# alarmClock.net
KiCad netlist of a schematic drawn in EAGLE
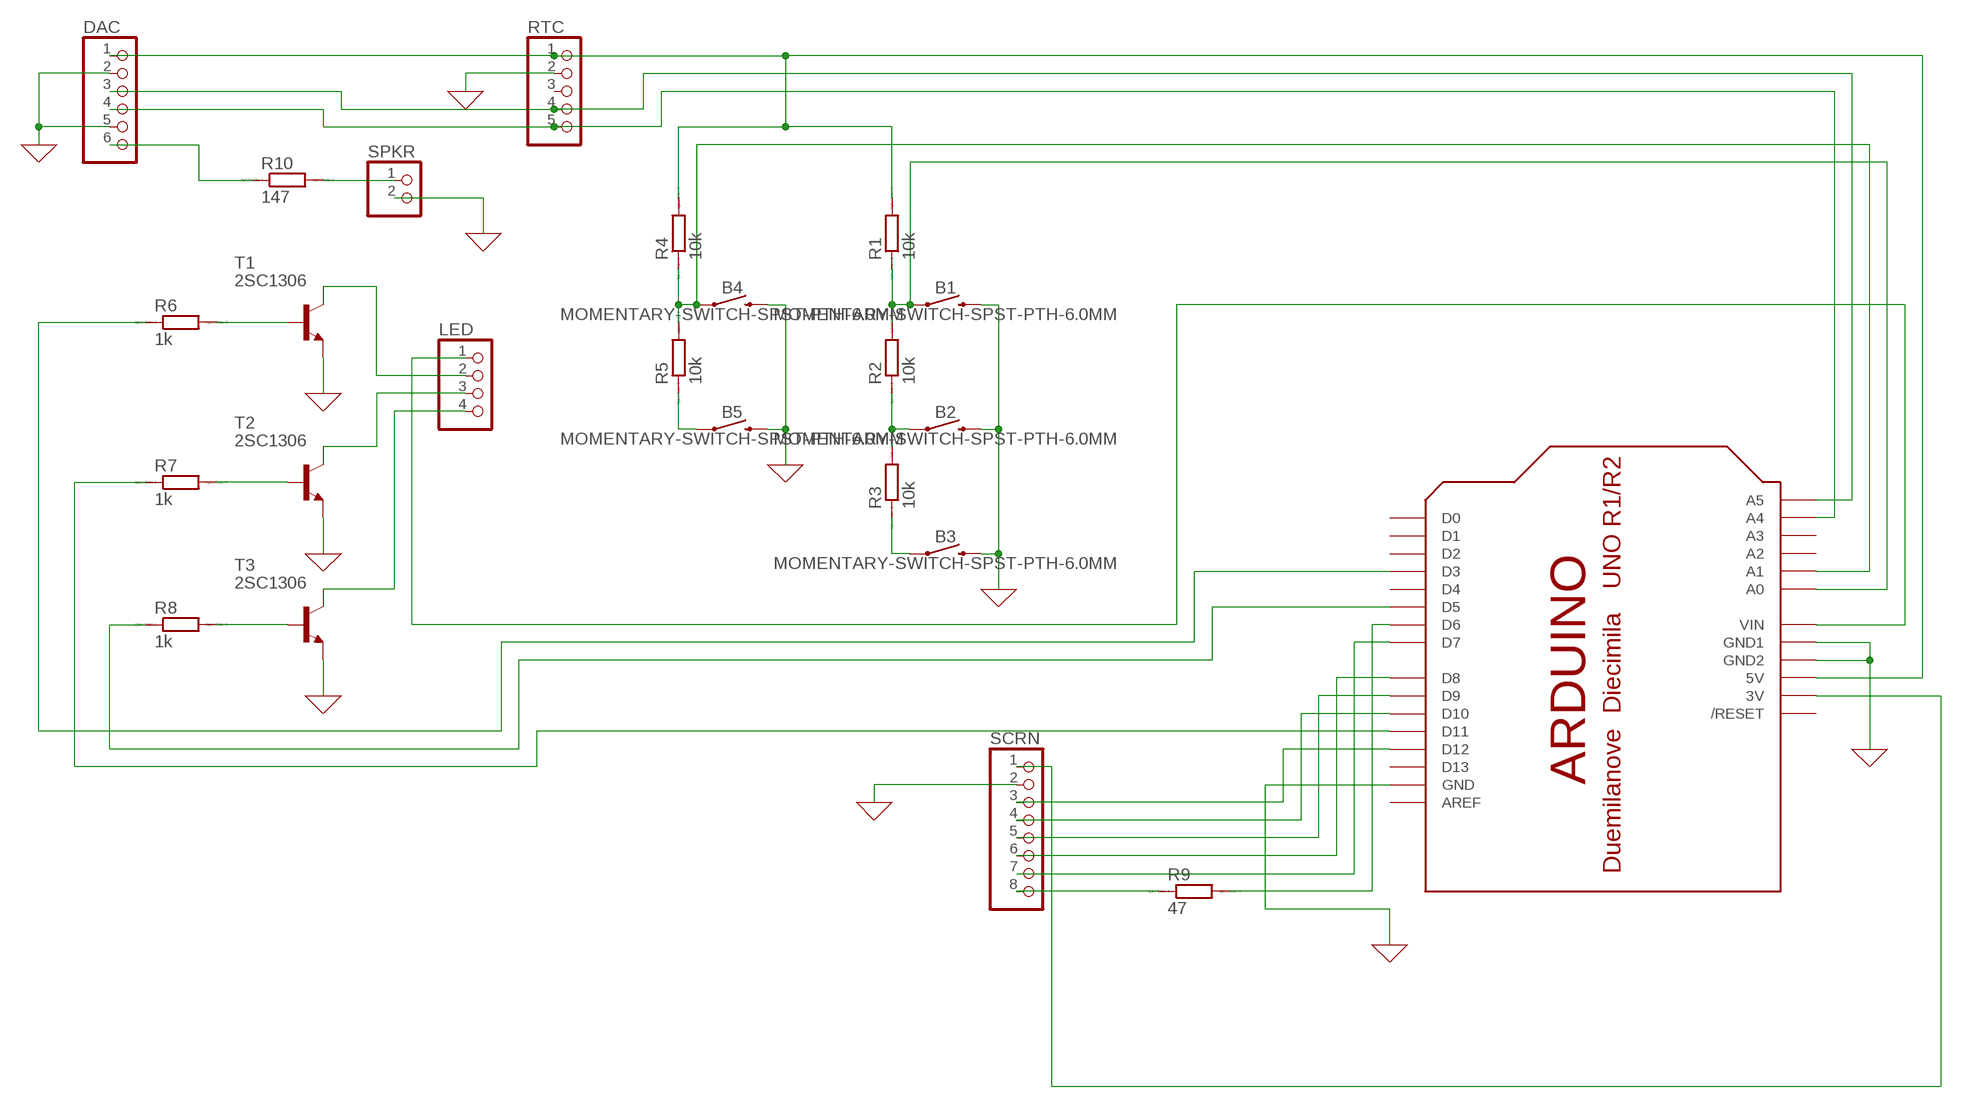
[diagram p0: schematic, sheet 1]

(export (version "E")
  (design (tool "Eeschema 10.0.6"))
  (components
    (comp (ref "B1")
      (value "MOMENTARY-SWITCH-SPST-PTH-6.0MM")
      (footprint "eagle-import:TACTILE_SWITCH_PTH_6.0MM")
      (libsource (lib "eagle-import") (part "MOMENTARY-SWITCH-SPST-PTH-6.0MM"))
    )
    (comp (ref "B2")
      (value "MOMENTARY-SWITCH-SPST-PTH-6.0MM")
      (footprint "eagle-import:TACTILE_SWITCH_PTH_6.0MM")
      (libsource (lib "eagle-import") (part "MOMENTARY-SWITCH-SPST-PTH-6.0MM"))
    )
    (comp (ref "B3")
      (value "MOMENTARY-SWITCH-SPST-PTH-6.0MM")
      (footprint "eagle-import:TACTILE_SWITCH_PTH_6.0MM")
      (libsource (lib "eagle-import") (part "MOMENTARY-SWITCH-SPST-PTH-6.0MM"))
    )
    (comp (ref "B4")
      (value "MOMENTARY-SWITCH-SPST-PTH-6.0MM")
      (footprint "eagle-import:TACTILE_SWITCH_PTH_6.0MM")
      (libsource (lib "eagle-import") (part "MOMENTARY-SWITCH-SPST-PTH-6.0MM"))
    )
    (comp (ref "B5")
      (value "MOMENTARY-SWITCH-SPST-PTH-6.0MM")
      (footprint "eagle-import:TACTILE_SWITCH_PTH_6.0MM")
      (libsource (lib "eagle-import") (part "MOMENTARY-SWITCH-SPST-PTH-6.0MM"))
    )
    (comp (ref "DAC")
      (value "PINHD-1X6")
      (footprint "eagle-import:1X06")
      (libsource (lib "eagle-import") (part "PINHD-1X6"))
    )
    (comp (ref "LED")
      (value "PINHD-1X4")
      (footprint "eagle-import:1X04")
      (libsource (lib "eagle-import") (part "PINHD-1X4"))
    )
    (comp (ref "R1")
      (value "10k")
      (footprint "eagle-import:0204_7")
      (libsource (lib "eagle-import") (part "R0204/7"))
    )
    (comp (ref "R2")
      (value "10k")
      (footprint "eagle-import:0204_7")
      (libsource (lib "eagle-import") (part "R0204/7"))
    )
    (comp (ref "R3")
      (value "10k")
      (footprint "eagle-import:0204_7")
      (libsource (lib "eagle-import") (part "R0204/7"))
    )
    (comp (ref "R4")
      (value "10k")
      (footprint "eagle-import:0204_7")
      (libsource (lib "eagle-import") (part "R0204/7"))
    )
    (comp (ref "R5")
      (value "10k")
      (footprint "eagle-import:0204_7")
      (libsource (lib "eagle-import") (part "R0204/7"))
    )
    (comp (ref "R6")
      (value "1k")
      (footprint "eagle-import:0204_7")
      (libsource (lib "eagle-import") (part "R0204/7"))
    )
    (comp (ref "R7")
      (value "1k")
      (footprint "eagle-import:0204_7")
      (libsource (lib "eagle-import") (part "R0204/7"))
    )
    (comp (ref "R8")
      (value "1k")
      (footprint "eagle-import:0204_7")
      (libsource (lib "eagle-import") (part "R0204/7"))
    )
    (comp (ref "R9")
      (value "47")
      (footprint "eagle-import:0204_7")
      (libsource (lib "eagle-import") (part "R0204/7"))
    )
    (comp (ref "R10")
      (value "147")
      (footprint "eagle-import:0204_7")
      (libsource (lib "eagle-import") (part "R0204/7"))
    )
    (comp (ref "RTC")
      (value "PINHD-1X5")
      (footprint "eagle-import:1X05")
      (libsource (lib "eagle-import") (part "PINHD-1X5"))
    )
    (comp (ref "SCRN")
      (value "PINHD-1X8")
      (footprint "eagle-import:1X08")
      (libsource (lib "eagle-import") (part "PINHD-1X8"))
    )
    (comp (ref "SPKR")
      (value "PINHD-1X2")
      (footprint "eagle-import:1X02")
      (libsource (lib "eagle-import") (part "PINHD-1X2"))
    )
    (comp (ref "T1")
      (value "2SC1306")
      (footprint "eagle-import:TO220BV")
      (libsource (lib "eagle-import") (part "2SC1306"))
    )
    (comp (ref "T2")
      (value "2SC1306")
      (footprint "eagle-import:TO220BV")
      (libsource (lib "eagle-import") (part "2SC1306"))
    )
    (comp (ref "T3")
      (value "2SC1306")
      (footprint "eagle-import:TO220BV")
      (libsource (lib "eagle-import") (part "2SC1306"))
    )
    (comp (ref "U$1")
      (value "ARDUINOUNO")
      (footprint "eagle-import:ARDUINO")
      (libsource (lib "eagle-import") (part "ARDUINOUNO"))
    )
  )
  (nets
    (net (code "1") (name "GND") (class "Default")
      (node (ref "B1") (pin "3") (pinfunction "2_3") (pintype "passive"))
      (node (ref "B2") (pin "3") (pinfunction "2_3") (pintype "passive"))
      (node (ref "B3") (pin "3") (pinfunction "2_3") (pintype "passive"))
      (node (ref "B4") (pin "3") (pinfunction "2_3") (pintype "passive"))
      (node (ref "B5") (pin "3") (pinfunction "2_3") (pintype "passive"))
      (node (ref "DAC") (pin "2") (pinfunction "2_2") (pintype "passive"))
      (node (ref "DAC") (pin "5") (pinfunction "5_5") (pintype "passive"))
      (node (ref "RTC") (pin "2") (pinfunction "2_2") (pintype "passive"))
      (node (ref "SCRN") (pin "2") (pinfunction "2_2") (pintype "passive"))
      (node (ref "SPKR") (pin "2") (pinfunction "2_2") (pintype "passive"))
      (node (ref "T1") (pin "3") (pinfunction "E_3") (pintype "passive"))
      (node (ref "T2") (pin "3") (pinfunction "E_3") (pintype "passive"))
      (node (ref "T3") (pin "3") (pinfunction "E_3") (pintype "passive"))
      (node (ref "U$1") (pin "GND") (pinfunction "GND_GND") (pintype "power_in"))
      (node (ref "U$1") (pin "GND1") (pinfunction "GND1_GND1") (pintype "power_in"))
      (node (ref "U$1") (pin "GND2") (pinfunction "GND2_GND2") (pintype "power_in"))
    )
    (net (code "2") (name "Net-(B1-Pad1)") (class "Default")
      (node (ref "B1") (pin "1") (pinfunction "1_1") (pintype "passive"))
      (node (ref "R1") (pin "1") (pinfunction "1_1") (pintype "passive"))
      (node (ref "R2") (pin "2") (pinfunction "2_2") (pintype "passive"))
      (node (ref "U$1") (pin "A0") (pinfunction "A0_A0") (pintype "bidirectional"))
    )
    (net (code "3") (name "Net-(B2-Pad1)") (class "Default")
      (node (ref "B2") (pin "1") (pinfunction "1_1") (pintype "passive"))
      (node (ref "R2") (pin "1") (pinfunction "1_1") (pintype "passive"))
      (node (ref "R3") (pin "2") (pinfunction "2_2") (pintype "passive"))
    )
    (net (code "4") (name "Net-(B3-Pad1)") (class "Default")
      (node (ref "B3") (pin "1") (pinfunction "1_1") (pintype "passive"))
      (node (ref "R3") (pin "1") (pinfunction "1_1") (pintype "passive"))
    )
    (net (code "5") (name "Net-(B4-Pad1)") (class "Default")
      (node (ref "B4") (pin "1") (pinfunction "1_1") (pintype "passive"))
      (node (ref "R4") (pin "1") (pinfunction "1_1") (pintype "passive"))
      (node (ref "R5") (pin "2") (pinfunction "2_2") (pintype "passive"))
      (node (ref "U$1") (pin "A1") (pinfunction "A1_A1") (pintype "bidirectional"))
    )
    (net (code "6") (name "Net-(B5-Pad1)") (class "Default")
      (node (ref "B5") (pin "1") (pinfunction "1_1") (pintype "passive"))
      (node (ref "R5") (pin "1") (pinfunction "1_1") (pintype "passive"))
    )
    (net (code "7") (name "Net-(DAC-Pad1)") (class "Default")
      (node (ref "DAC") (pin "1") (pinfunction "1_1") (pintype "passive"))
      (node (ref "R1") (pin "2") (pinfunction "2_2") (pintype "passive"))
      (node (ref "R4") (pin "2") (pinfunction "2_2") (pintype "passive"))
      (node (ref "RTC") (pin "1") (pinfunction "1_1") (pintype "passive"))
      (node (ref "U$1") (pin "5V") (pinfunction "5V_5V") (pintype "power_in"))
    )
    (net (code "8") (name "Net-(DAC-Pad3)") (class "Default")
      (node (ref "DAC") (pin "3") (pinfunction "3_3") (pintype "passive"))
      (node (ref "RTC") (pin "4") (pinfunction "4_4") (pintype "passive"))
      (node (ref "U$1") (pin "A5") (pinfunction "A5_A5") (pintype "bidirectional"))
    )
    (net (code "9") (name "Net-(DAC-Pad4)") (class "Default")
      (node (ref "DAC") (pin "4") (pinfunction "4_4") (pintype "passive"))
      (node (ref "RTC") (pin "5") (pinfunction "5_5") (pintype "passive"))
      (node (ref "U$1") (pin "A4") (pinfunction "A4_A4") (pintype "bidirectional"))
    )
    (net (code "10") (name "Net-(DAC-Pad6)") (class "Default")
      (node (ref "DAC") (pin "6") (pinfunction "6_6") (pintype "passive"))
      (node (ref "R10") (pin "1") (pinfunction "1_1") (pintype "passive"))
    )
    (net (code "11") (name "Net-(LED-Pad1)") (class "Default")
      (node (ref "LED") (pin "1") (pinfunction "1_1") (pintype "passive"))
      (node (ref "U$1") (pin "VIN") (pinfunction "VIN_VIN") (pintype "power_in"))
    )
    (net (code "12") (name "Net-(R6-Pad1)") (class "Default")
      (node (ref "R6") (pin "1") (pinfunction "1_1") (pintype "passive"))
      (node (ref "U$1") (pin "D3") (pinfunction "D3_D3") (pintype "bidirectional"))
    )
    (net (code "13") (name "Net-(R7-Pad1)") (class "Default")
      (node (ref "R7") (pin "1") (pinfunction "1_1") (pintype "passive"))
      (node (ref "U$1") (pin "D11") (pinfunction "D11_D11") (pintype "bidirectional"))
    )
    (net (code "14") (name "Net-(R8-Pad1)") (class "Default")
      (node (ref "R8") (pin "1") (pinfunction "1_1") (pintype "passive"))
      (node (ref "U$1") (pin "D5") (pinfunction "D5_D5") (pintype "bidirectional"))
    )
    (net (code "15") (name "Net-(R9-Pad1)") (class "Default")
      (node (ref "R9") (pin "1") (pinfunction "1_1") (pintype "passive"))
      (node (ref "SCRN") (pin "8") (pinfunction "8_8") (pintype "passive"))
    )
    (net (code "16") (name "Net-(R9-Pad2)") (class "Default")
      (node (ref "R9") (pin "2") (pinfunction "2_2") (pintype "passive"))
      (node (ref "U$1") (pin "D6") (pinfunction "D6_D6") (pintype "bidirectional"))
    )
    (net (code "17") (name "Net-(R10-Pad2)") (class "Default")
      (node (ref "R10") (pin "2") (pinfunction "2_2") (pintype "passive"))
      (node (ref "SPKR") (pin "1") (pinfunction "1_1") (pintype "passive"))
    )
    (net (code "18") (name "Net-(SCRN-Pad1)") (class "Default")
      (node (ref "SCRN") (pin "1") (pinfunction "1_1") (pintype "passive"))
      (node (ref "U$1") (pin "3V") (pinfunction "3V_3V") (pintype "power_in"))
    )
    (net (code "19") (name "Net-(SCRN-Pad3)") (class "Default")
      (node (ref "SCRN") (pin "3") (pinfunction "3_3") (pintype "passive"))
      (node (ref "U$1") (pin "D12") (pinfunction "D12_D12") (pintype "bidirectional"))
    )
    (net (code "20") (name "Net-(SCRN-Pad4)") (class "Default")
      (node (ref "SCRN") (pin "4") (pinfunction "4_4") (pintype "passive"))
      (node (ref "U$1") (pin "D10") (pinfunction "D10_D10") (pintype "bidirectional"))
    )
    (net (code "21") (name "Net-(SCRN-Pad5)") (class "Default")
      (node (ref "SCRN") (pin "5") (pinfunction "5_5") (pintype "passive"))
      (node (ref "U$1") (pin "D9") (pinfunction "D9_D9") (pintype "bidirectional"))
    )
    (net (code "22") (name "Net-(SCRN-Pad6)") (class "Default")
      (node (ref "SCRN") (pin "6") (pinfunction "6_6") (pintype "passive"))
      (node (ref "U$1") (pin "D8") (pinfunction "D8_D8") (pintype "bidirectional"))
    )
    (net (code "23") (name "Net-(SCRN-Pad7)") (class "Default")
      (node (ref "SCRN") (pin "7") (pinfunction "7_7") (pintype "passive"))
      (node (ref "U$1") (pin "D7") (pinfunction "D7_D7") (pintype "bidirectional"))
    )
    (net (code "24") (name "Net-(T1-B)") (class "Default")
      (node (ref "R6") (pin "2") (pinfunction "2_2") (pintype "passive"))
      (node (ref "T1") (pin "1") (pinfunction "B_1") (pintype "passive"))
    )
    (net (code "25") (name "Net-(T1-C)") (class "Default")
      (node (ref "LED") (pin "2") (pinfunction "2_2") (pintype "passive"))
      (node (ref "T1") (pin "2") (pinfunction "C_2") (pintype "passive"))
    )
    (net (code "26") (name "Net-(T2-B)") (class "Default")
      (node (ref "R7") (pin "2") (pinfunction "2_2") (pintype "passive"))
      (node (ref "T2") (pin "1") (pinfunction "B_1") (pintype "passive"))
    )
    (net (code "27") (name "Net-(T2-C)") (class "Default")
      (node (ref "LED") (pin "3") (pinfunction "3_3") (pintype "passive"))
      (node (ref "T2") (pin "2") (pinfunction "C_2") (pintype "passive"))
    )
    (net (code "28") (name "Net-(T3-B)") (class "Default")
      (node (ref "R8") (pin "2") (pinfunction "2_2") (pintype "passive"))
      (node (ref "T3") (pin "1") (pinfunction "B_1") (pintype "passive"))
    )
    (net (code "29") (name "Net-(T3-C)") (class "Default")
      (node (ref "LED") (pin "4") (pinfunction "4_4") (pintype "passive"))
      (node (ref "T3") (pin "2") (pinfunction "C_2") (pintype "passive"))
    )
    (net (code "30") (name "unconnected-(RTC-Pad3)") (class "Default")
      (node (ref "RTC") (pin "3") (pinfunction "3_3") (pintype "passive"))
    )
    (net (code "31") (name "unconnected-(U$1-PadA2)") (class "Default")
      (node (ref "U$1") (pin "A2") (pinfunction "A2_A2") (pintype "bidirectional"))
    )
    (net (code "32") (name "unconnected-(U$1-PadA3)") (class "Default")
      (node (ref "U$1") (pin "A3") (pinfunction "A3_A3") (pintype "bidirectional"))
    )
    (net (code "33") (name "unconnected-(U$1-PadAREF)") (class "Default")
      (node (ref "U$1") (pin "AREF") (pinfunction "AREF_AREF") (pintype "bidirectional"))
    )
    (net (code "34") (name "unconnected-(U$1-PadD0)") (class "Default")
      (node (ref "U$1") (pin "D0") (pinfunction "D0_D0") (pintype "bidirectional"))
    )
    (net (code "35") (name "unconnected-(U$1-PadD1)") (class "Default")
      (node (ref "U$1") (pin "D1") (pinfunction "D1_D1") (pintype "bidirectional"))
    )
    (net (code "36") (name "unconnected-(U$1-PadD2)") (class "Default")
      (node (ref "U$1") (pin "D2") (pinfunction "D2_D2") (pintype "bidirectional"))
    )
    (net (code "37") (name "unconnected-(U$1-PadD4)") (class "Default")
      (node (ref "U$1") (pin "D4") (pinfunction "D4_D4") (pintype "bidirectional"))
    )
    (net (code "38") (name "unconnected-(U$1-PadD13)") (class "Default")
      (node (ref "U$1") (pin "D13") (pinfunction "D13_D13") (pintype "bidirectional"))
    )
    (net (code "39") (name "unconnected-(U$1-{slash}RESET-PadRESET)") (class "Default")
      (node (ref "U$1") (pin "RESET") (pinfunction "/RESET_RESET") (pintype "bidirectional"))
    )
  )
)
